# N2_Avionics_board.net
KiCad netlist of a schematic drawn in EasyEDA
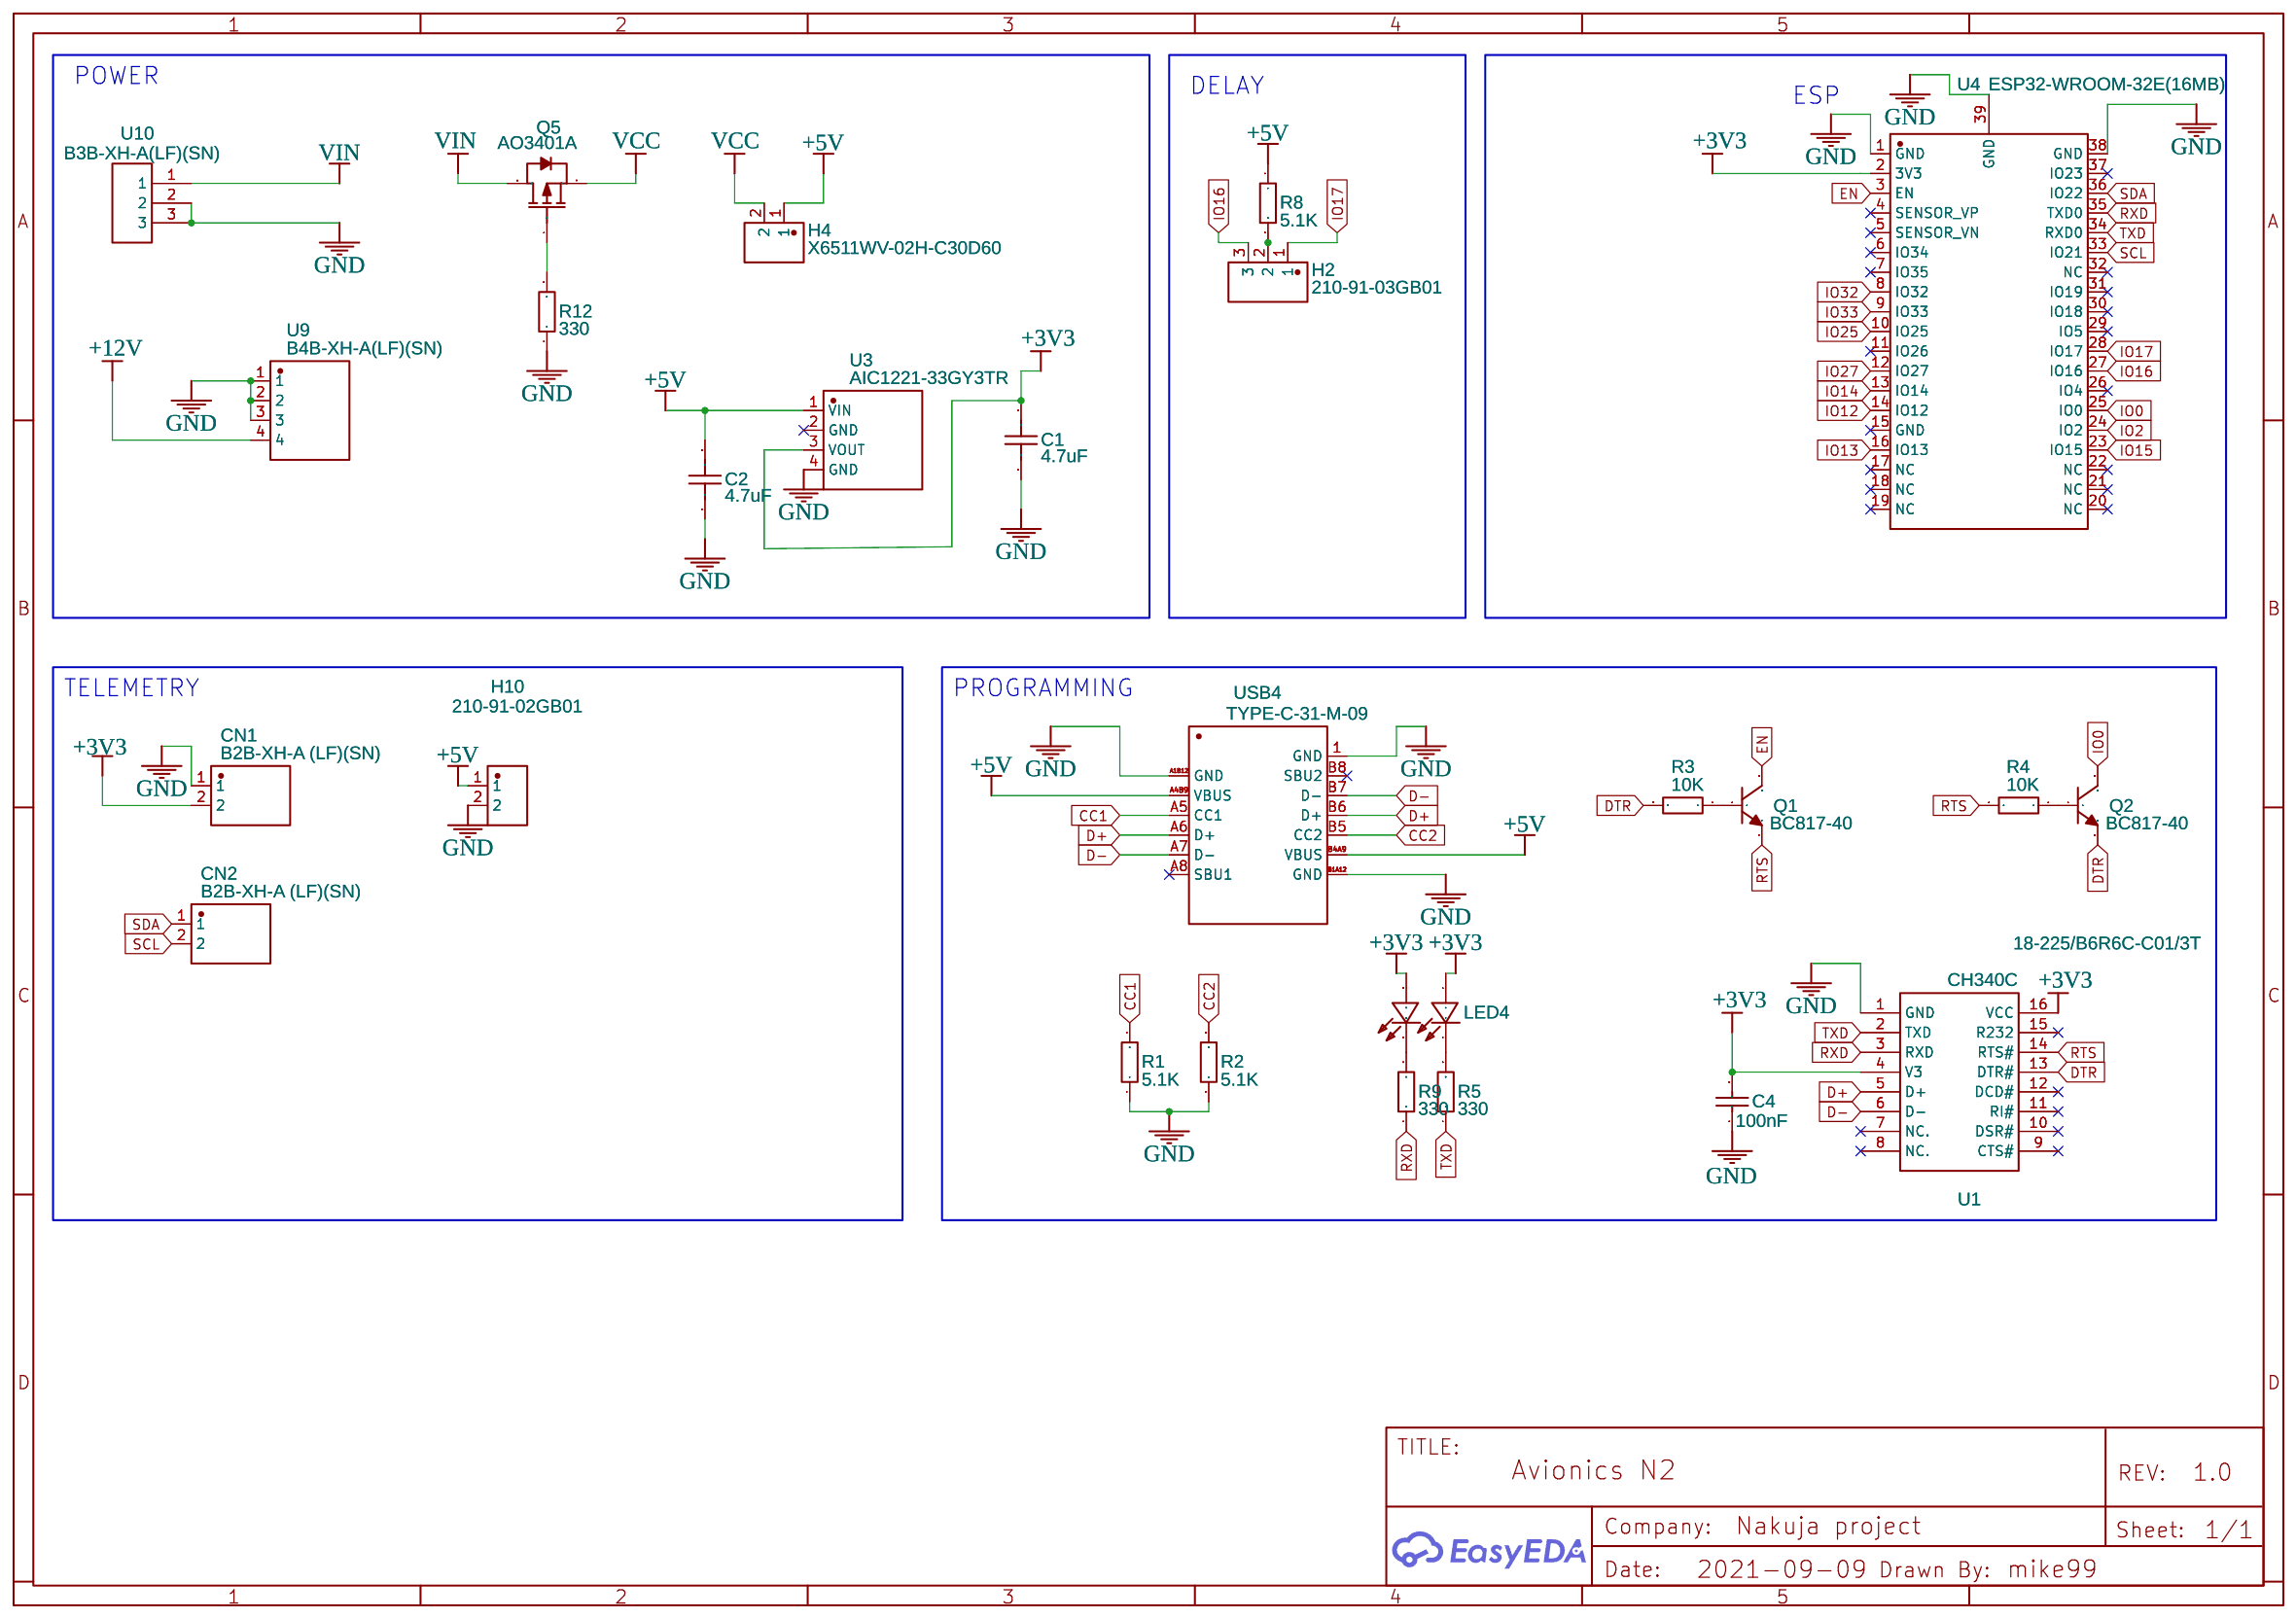
[diagram p0: Sheet_1]
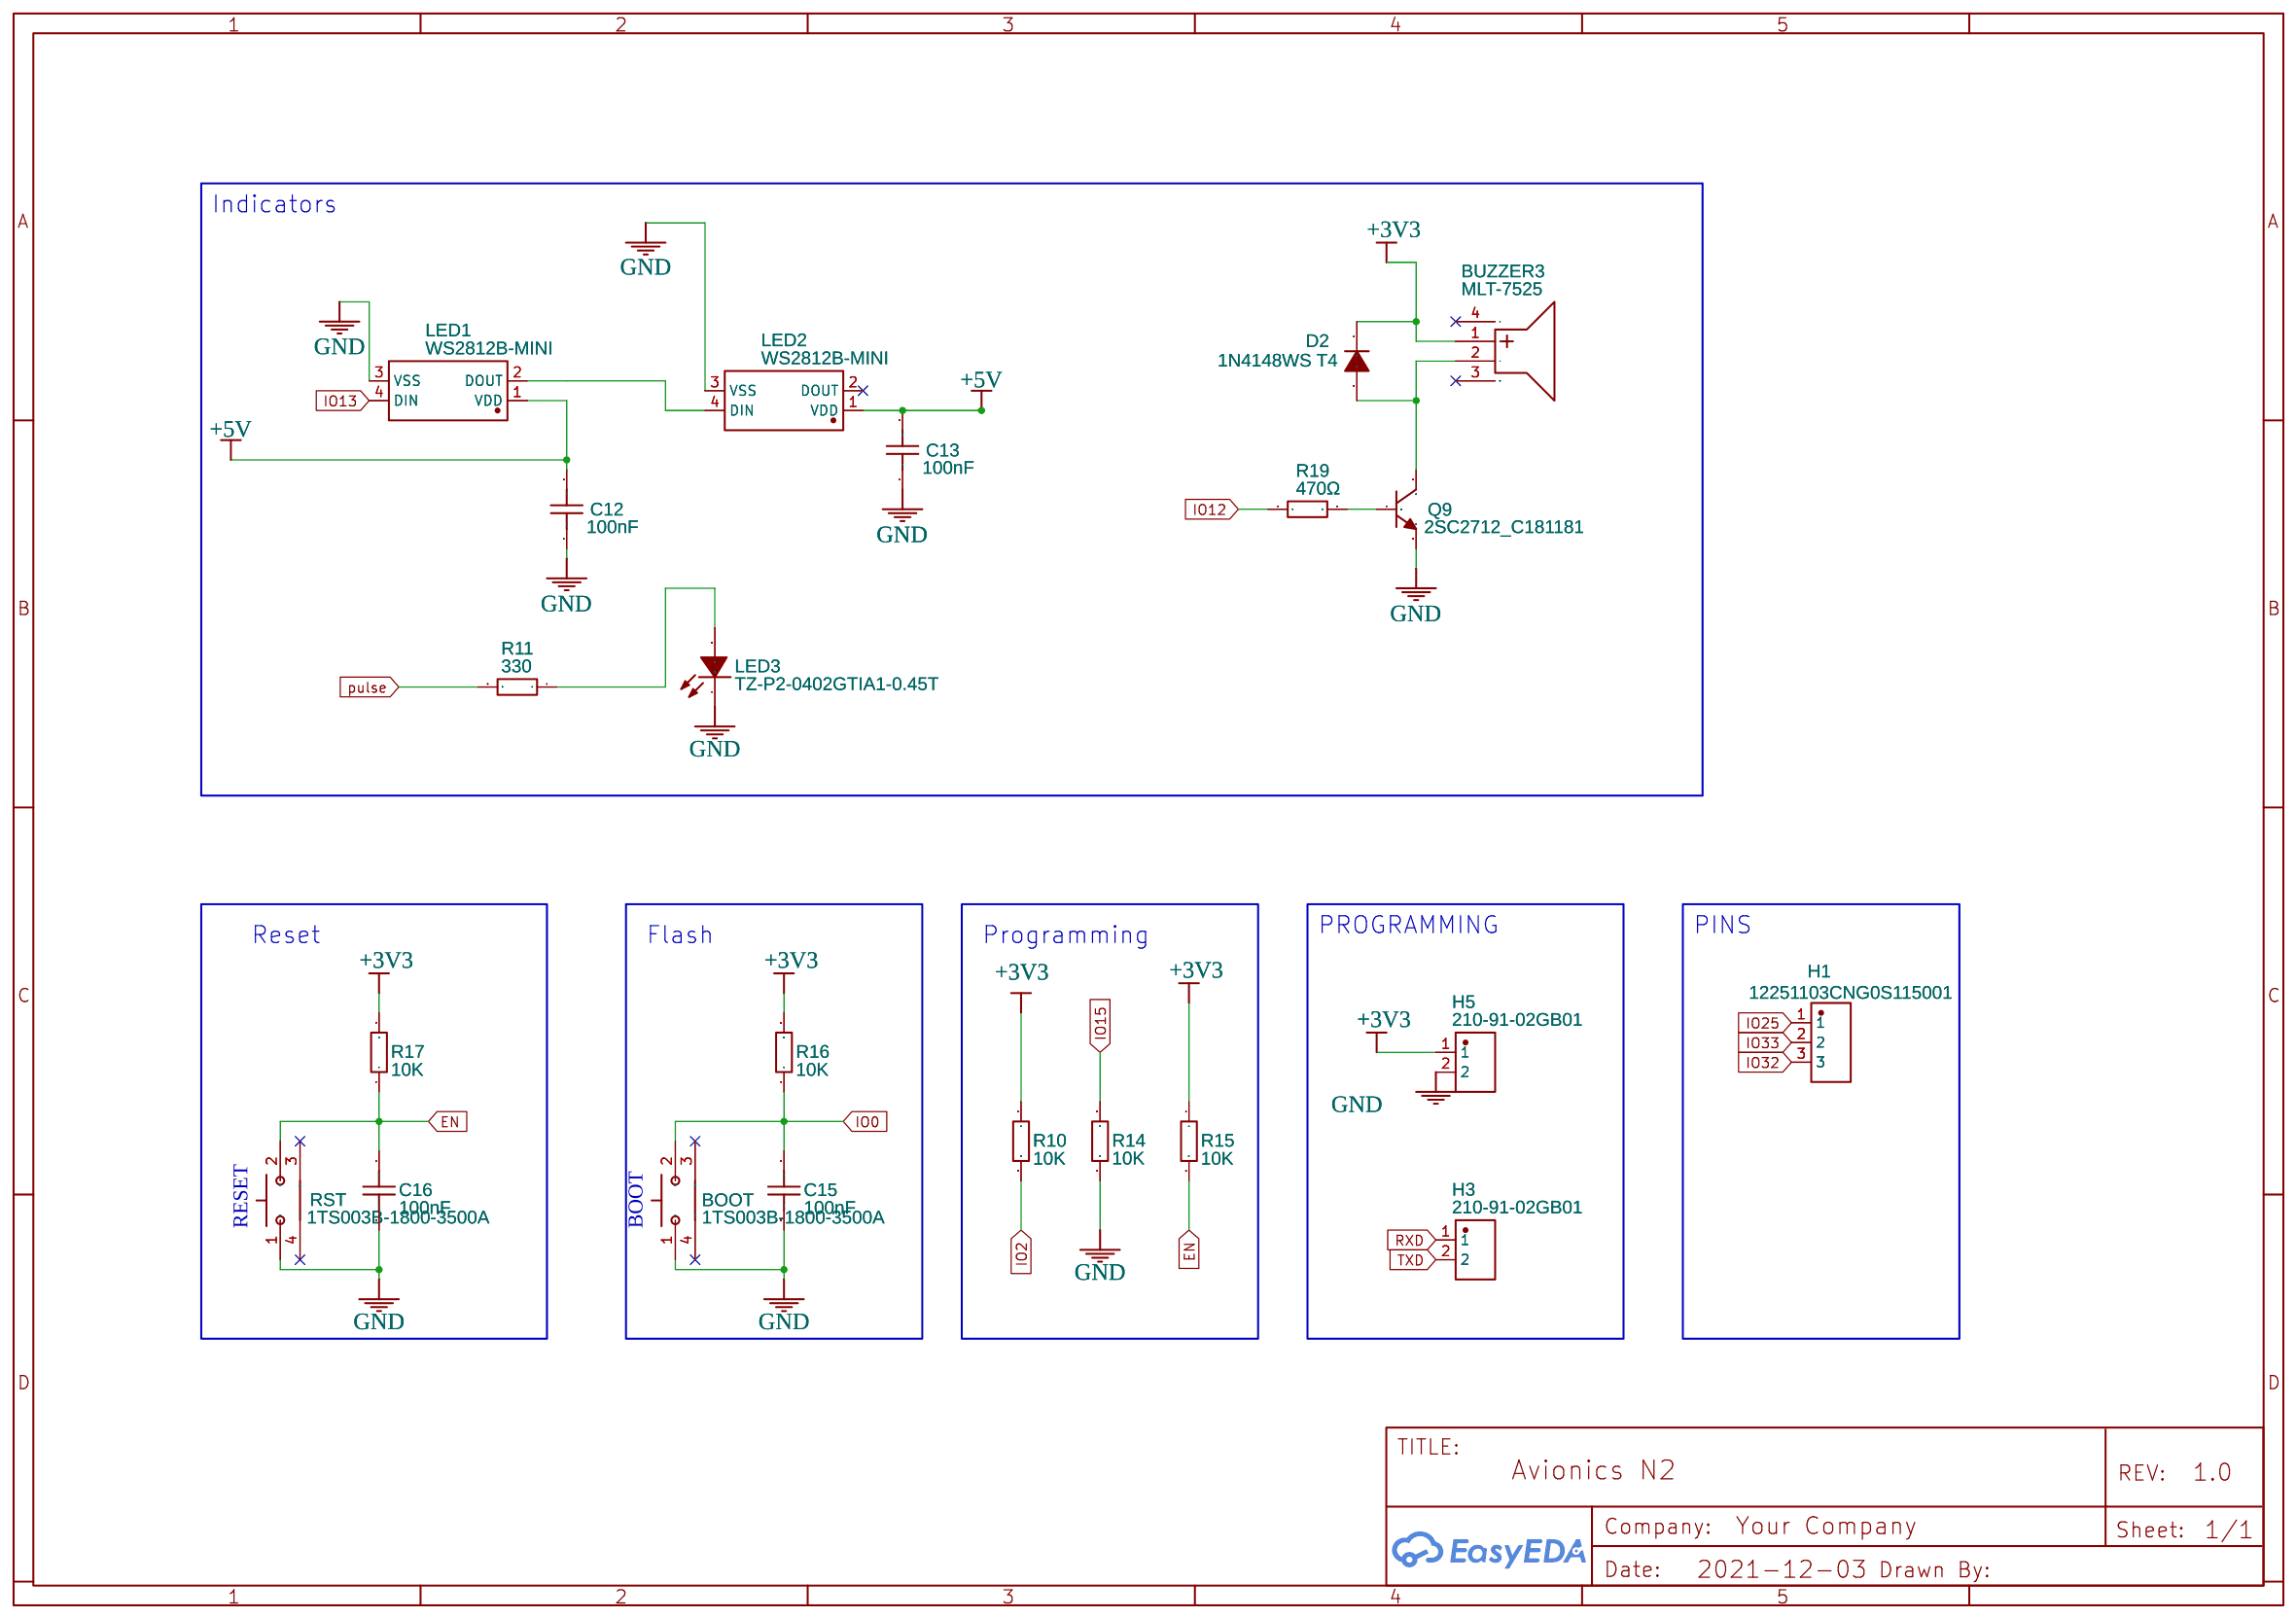
[diagram p1: Sheet_2]
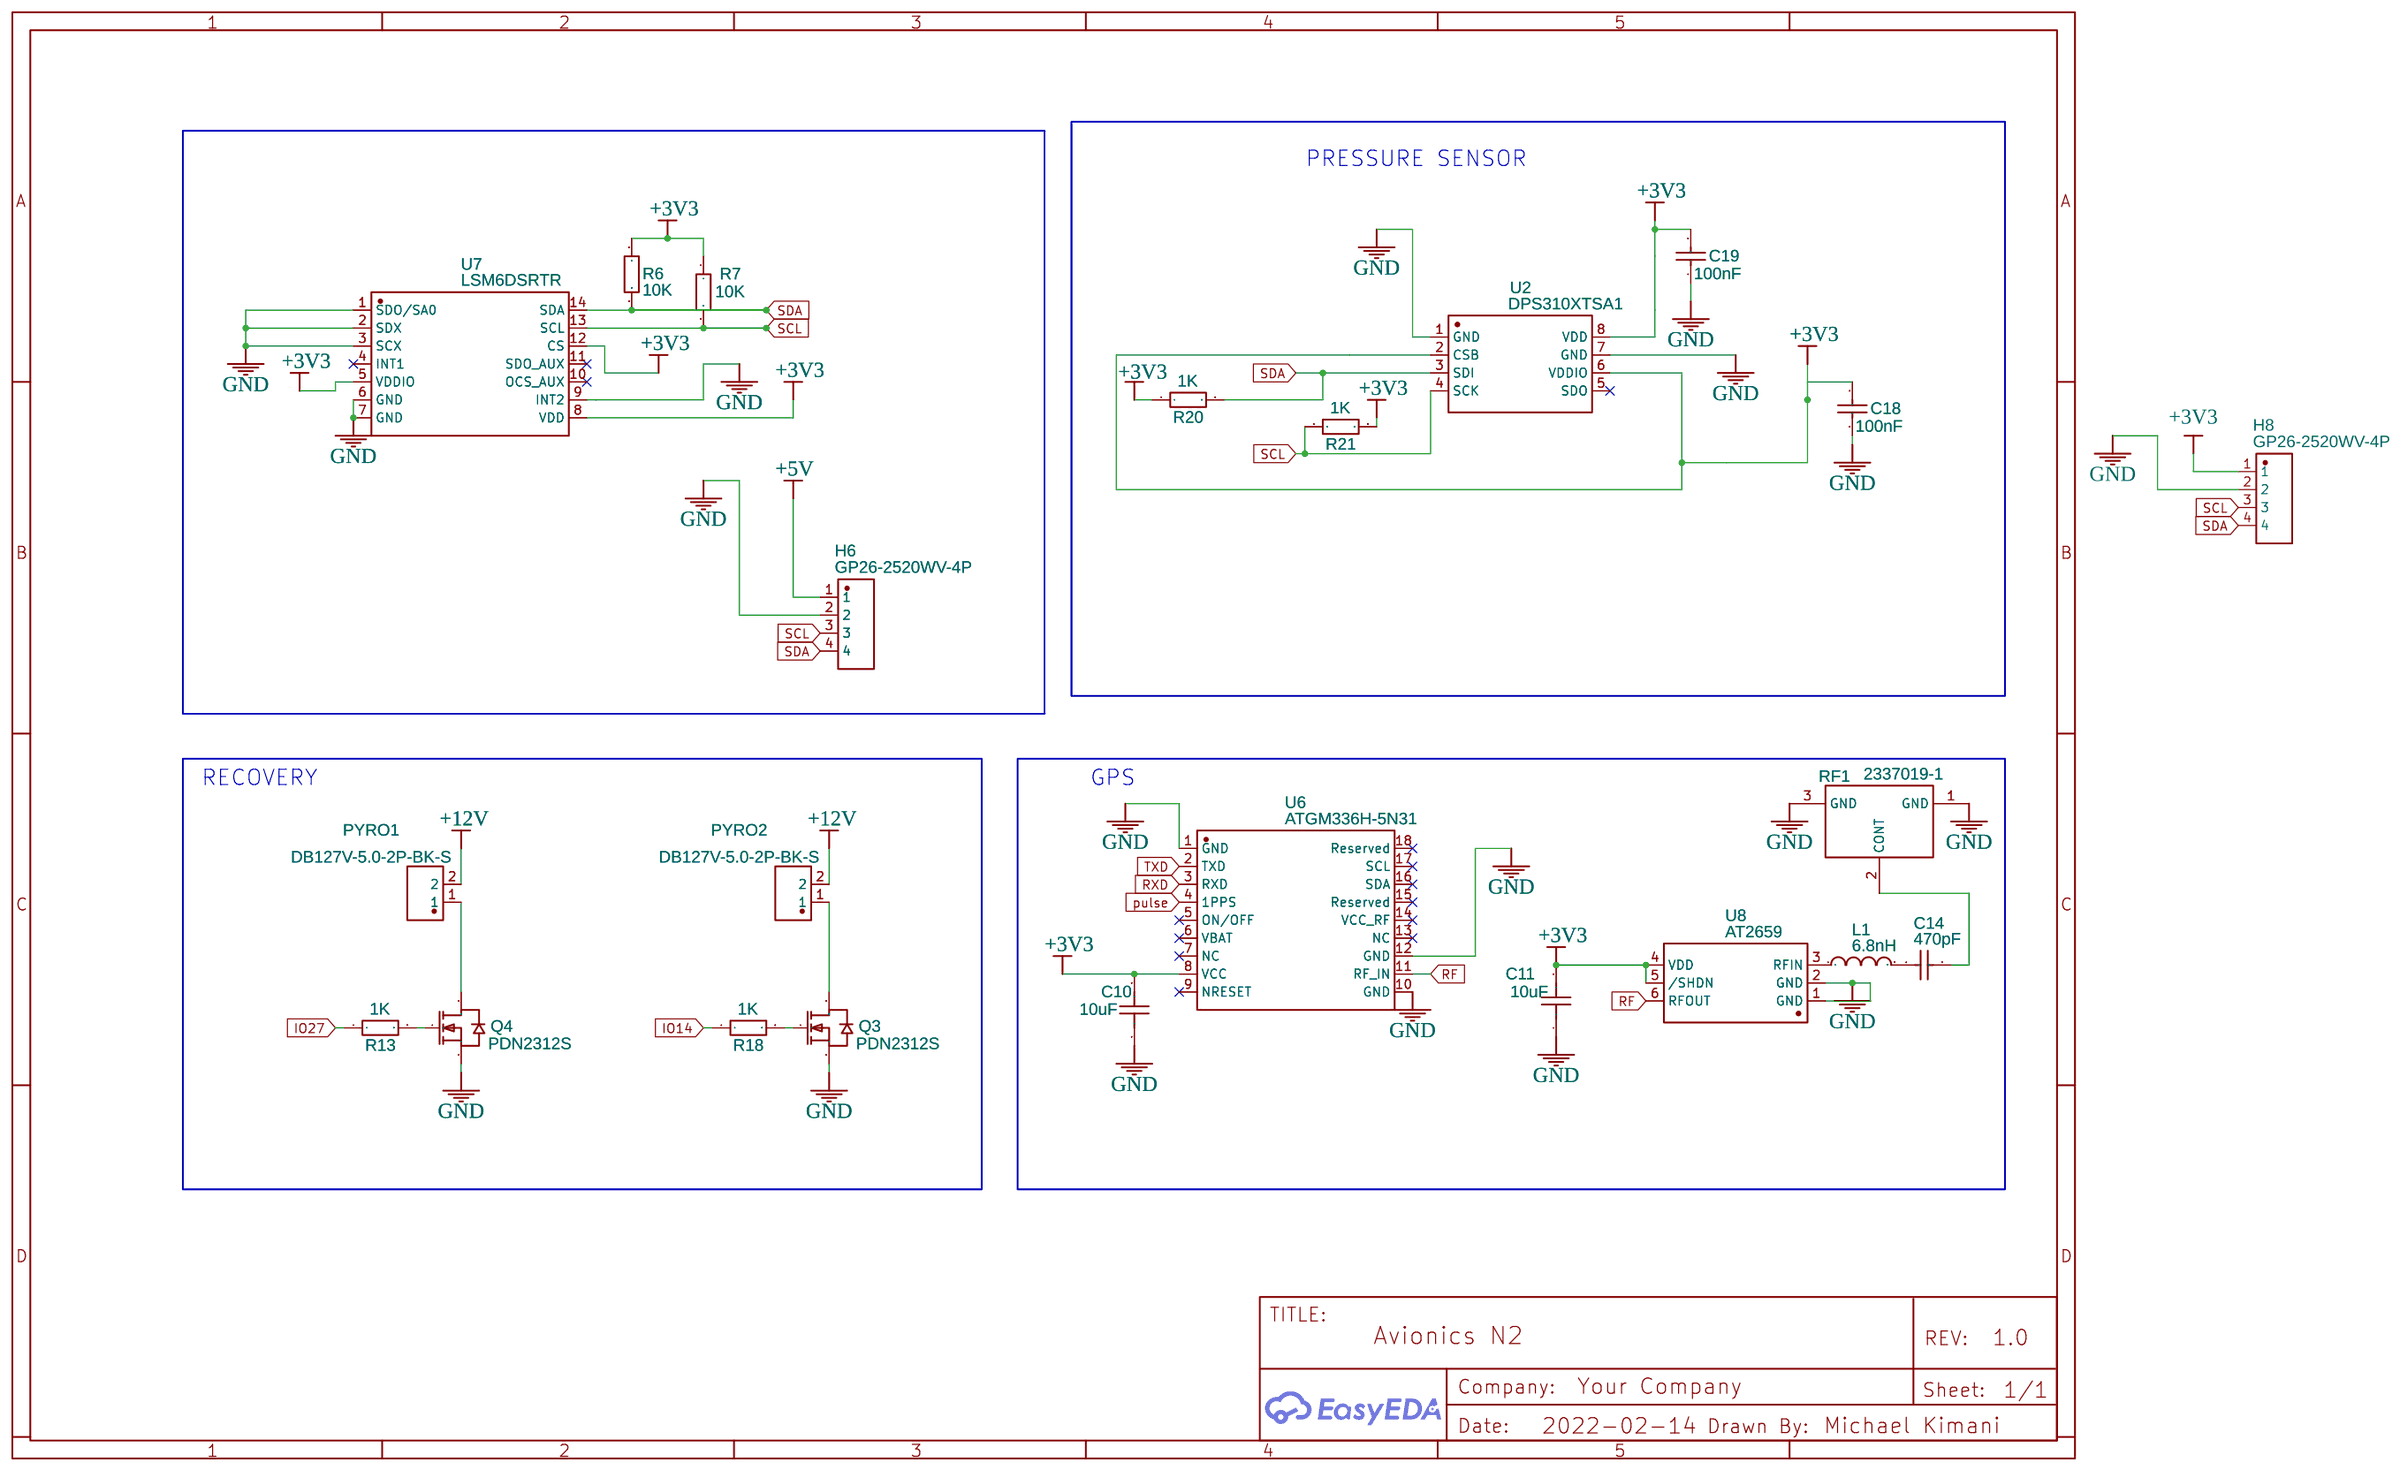
[diagram p2: Sheet_3]

(export (version "E")
  (design (tool "Eeschema 10.0.6"))
  (components
    (comp (ref "C1")
      (value "4.7uF")
      (fields
        (field (name "BOM_Manufacturer Part") "CL05A475MO5NUNC")
        (field (name "BOM_Supplier Part") "C318563")
      )
      (libsource (lib "") (part "CL05A475MO5NUNC"))
    )
    (comp (ref "C2")
      (value "4.7uF")
      (fields
        (field (name "BOM_Manufacturer Part") "CL05A475MO5NUNC")
        (field (name "BOM_Supplier Part") "C318563")
      )
      (libsource (lib "") (part "CL05A475MO5NUNC"))
    )
    (comp (ref "C4")
      (value "100nF")
      (fields
        (field (name "BOM_Manufacturer Part") "0603B104K250")
        (field (name "BOM_Supplier Part") "C83054")
      )
      (libsource (lib "") (part "0603B104K250"))
    )
    (comp (ref "CN1")
      (value "B2B-XH-A (LF)(SN)")
      (fields (field (name "BOM_Supplier Part") "C158012"))
      (libsource (lib "") (part "B2B-XH-A (LF)(SN)"))
    )
    (comp (ref "CN2")
      (value "B2B-XH-A (LF)(SN)")
      (fields (field (name "BOM_Supplier Part") "C158012"))
      (libsource (lib "") (part "B2B-XH-A (LF)(SN)"))
    )
    (comp (ref "H2")
      (value "210-91-03GB01")
      (fields (field (name "BOM_Supplier Part") "C390679"))
      (libsource (lib "") (part "210-91-03GB01"))
    )
    (comp (ref "H4")
      (value "X6511WV-02H-C30D60")
      (fields (field (name "BOM_Supplier Part") "C706874"))
      (libsource (lib "") (part "X6511WV-02H-C30D60"))
    )
    (comp (ref "H10")
      (value "210-91-02GB01")
      (fields (field (name "BOM_Supplier Part") "C390678"))
      (libsource (lib "") (part "210-91-02GB01"))
    )
    (comp (ref "LED4")
      (value "18-225/B6R6C-C01/3T")
      (fields (field (name "BOM_Supplier Part") "C282127"))
      (libsource (lib "") (part "18-225/B6R6C-C01/3T"))
    )
    (comp (ref "Q1")
      (value "BC817-40")
      (fields (field (name "BOM_Supplier Part") "C181151"))
      (libsource (lib "") (part "BC817-40"))
    )
    (comp (ref "Q2")
      (value "BC817-40")
      (fields (field (name "BOM_Supplier Part") "C181151"))
      (libsource (lib "") (part "BC817-40"))
    )
    (comp (ref "Q5")
      (value "AO3401A")
      (fields (field (name "BOM_Supplier Part") "C15127"))
      (libsource (lib "") (part "AO3401A"))
    )
    (comp (ref "R1")
      (value "5.1K")
      (fields
        (field (name "BOM_Manufacturer Part") "0402WGF5101TCE")
        (field (name "BOM_Supplier Part") "C25905")
      )
      (libsource (lib "") (part "0402WGF5101TCE"))
    )
    (comp (ref "R2")
      (value "5.1K")
      (fields
        (field (name "BOM_Manufacturer Part") "0402WGF5101TCE")
        (field (name "BOM_Supplier Part") "C25905")
      )
      (libsource (lib "") (part "0402WGF5101TCE"))
    )
    (comp (ref "R3")
      (value "10K")
      (fields
        (field (name "BOM_Manufacturer Part") "RTT02103JTH")
        (field (name "BOM_Supplier Part") "C102759")
      )
      (libsource (lib "") (part "RTT02103JTH"))
    )
    (comp (ref "R4")
      (value "10K")
      (fields
        (field (name "BOM_Manufacturer Part") "RTT02103JTH")
        (field (name "BOM_Supplier Part") "C102759")
      )
      (libsource (lib "") (part "RTT02103JTH"))
    )
    (comp (ref "R5")
      (value "330")
      (fields
        (field (name "BOM_Manufacturer Part") "0402WGJ0331TCE")
        (field (name "BOM_Supplier Part") "C12246")
      )
      (libsource (lib "") (part "0402WGJ0331TCE"))
    )
    (comp (ref "R8")
      (value "5.1K")
      (fields
        (field (name "BOM_Manufacturer Part") "0402WGF5101TCE")
        (field (name "BOM_Supplier Part") "C25905")
      )
      (libsource (lib "") (part "0402WGF5101TCE_1"))
    )
    (comp (ref "R9")
      (value "330")
      (fields
        (field (name "BOM_Manufacturer Part") "0402WGJ0331TCE")
        (field (name "BOM_Supplier Part") "C12246")
      )
      (libsource (lib "") (part "0402WGJ0331TCE"))
    )
    (comp (ref "R12")
      (value "330")
      (fields
        (field (name "BOM_Manufacturer Part") "0402WGJ0331TCE")
        (field (name "BOM_Supplier Part") "C12246")
      )
      (libsource (lib "") (part "0402WGJ0331TCE"))
    )
    (comp (ref "U1")
      (value "CH340C")
      (fields (field (name "BOM_Supplier Part") "C84681"))
      (libsource (lib "") (part "CH340C"))
    )
    (comp (ref "U3")
      (value "AIC1221-33GY3TR")
      (fields (field (name "BOM_Supplier Part") "C211622"))
      (libsource (lib "") (part "AIC1221-33GY3TR"))
    )
    (comp (ref "U4")
      (value "ESP32-WROOM-32E(16MB)")
      (fields (field (name "BOM_Supplier Part") "C701343"))
      (libsource (lib "") (part "ESP32-WROOM-32E(16MB)"))
    )
    (comp (ref "U9")
      (value "B4B-XH-A(LF)(SN)")
      (fields (field (name "BOM_Supplier Part") "C144395"))
      (libsource (lib "") (part "B4B-XH-A(LF)(SN)"))
    )
    (comp (ref "U10")
      (value "B3B-XH-A(LF)(SN)")
      (fields (field (name "BOM_Supplier Part") "C144394"))
      (libsource (lib "") (part "B3B-XH-A(LF)(SN)"))
    )
    (comp (ref "USB4")
      (value "TYPE-C-31-M-09")
      (fields (field (name "BOM_Supplier Part") "C2689967"))
      (libsource (lib "") (part "TYPE-C-31-M-09"))
    )
    (comp (ref "BOOT")
      (value "1TS003B-1800-3500A")
      (fields (field (name "BOM_Supplier Part") "C255809"))
      (libsource (lib "") (part "1TS003B-1800-3500A_1"))
    )
    (comp (ref "BUZZER3")
      (value "MLT-7525")
      (fields (field (name "BOM_Supplier Part") "C95299"))
      (libsource (lib "") (part "MLT-7525"))
    )
    (comp (ref "C12")
      (value "100nF")
      (fields
        (field (name "BOM_Manufacturer Part") "CL05B104KB54PNC")
        (field (name "BOM_Supplier Part") "C307331")
      )
      (libsource (lib "") (part "CL05B104KB54PNC_1"))
    )
    (comp (ref "C13")
      (value "100nF")
      (fields
        (field (name "BOM_Manufacturer Part") "CL05B104KB54PNC")
        (field (name "BOM_Supplier Part") "C307331")
      )
      (libsource (lib "") (part "CL05B104KB54PNC_1"))
    )
    (comp (ref "C15")
      (value "100nF")
      (fields
        (field (name "BOM_Manufacturer Part") "CL05B104KB54PNC")
        (field (name "BOM_Supplier Part") "C307331")
      )
      (libsource (lib "") (part "CL05B104KB54PNC"))
    )
    (comp (ref "C16")
      (value "100nF")
      (fields
        (field (name "BOM_Manufacturer Part") "CL05B104KB54PNC")
        (field (name "BOM_Supplier Part") "C307331")
      )
      (libsource (lib "") (part "CL05B104KB54PNC"))
    )
    (comp (ref "D2")
      (value "1N4148WS T4")
      (fields (field (name "BOM_Supplier Part") "C2128"))
      (libsource (lib "") (part "1N4148WS T4"))
    )
    (comp (ref "H1")
      (value "12251103CNG0S115001")
      (fields (field (name "BOM_Supplier Part") "C429954"))
      (libsource (lib "") (part "12251103CNG0S115001"))
    )
    (comp (ref "H3")
      (value "210-91-02GB01")
      (fields (field (name "BOM_Supplier Part") "C390678"))
      (libsource (lib "") (part "210-91-02GB01"))
    )
    (comp (ref "H5")
      (value "210-91-02GB01")
      (fields (field (name "BOM_Supplier Part") "C390678"))
      (libsource (lib "") (part "210-91-02GB01"))
    )
    (comp (ref "LED1")
      (value "WS2812B-MINI")
      (fields
        (field (name "BOM_Manufacturer Part") "WS2812B-Mini")
        (field (name "BOM_Supplier Part") "C527089")
      )
      (libsource (lib "") (part "WS2812B-MINI"))
    )
    (comp (ref "LED2")
      (value "WS2812B-MINI")
      (fields
        (field (name "BOM_Manufacturer Part") "WS2812B-Mini")
        (field (name "BOM_Supplier Part") "C527089")
      )
      (libsource (lib "") (part "WS2812B-MINI"))
    )
    (comp (ref "LED3")
      (value "TZ-P2-0402GTIA1-0.45T")
      (fields (field (name "BOM_Supplier Part") "C688877"))
      (libsource (lib "") (part "TZ-P2-0402GTIA1-0.45T"))
    )
    (comp (ref "Q9")
      (value "2SC2712_C181181")
      (fields (field (name "BOM_Manufacturer Part") "2SC2712") (field (name "BOM_Supplier Part") "C181181"))
      (libsource (lib "") (part "2SC2712_C181181"))
    )
    (comp (ref "R10")
      (value "10K")
      (fields
        (field (name "BOM_Manufacturer Part") "RTT02103JTH")
        (field (name "BOM_Supplier Part") "C102759")
      )
      (libsource (lib "") (part "RTT02103JTH_1"))
    )
    (comp (ref "R11")
      (value "330")
      (fields
        (field (name "BOM_Manufacturer Part") "0402WGJ0331TCE")
        (field (name "BOM_Supplier Part") "C12246")
      )
      (libsource (lib "") (part "0402WGJ0331TCE"))
    )
    (comp (ref "R14")
      (value "10K")
      (fields
        (field (name "BOM_Manufacturer Part") "RTT02103JTH")
        (field (name "BOM_Supplier Part") "C102759")
      )
      (libsource (lib "") (part "RTT02103JTH"))
    )
    (comp (ref "R15")
      (value "10K")
      (fields
        (field (name "BOM_Manufacturer Part") "RTT02103JTH")
        (field (name "BOM_Supplier Part") "C102759")
      )
      (libsource (lib "") (part "RTT02103JTH_1"))
    )
    (comp (ref "R16")
      (value "10K")
      (fields
        (field (name "BOM_Manufacturer Part") "RTT02103JTH")
        (field (name "BOM_Supplier Part") "C102759")
      )
      (libsource (lib "") (part "RTT02103JTH"))
    )
    (comp (ref "R17")
      (value "10K")
      (fields
        (field (name "BOM_Manufacturer Part") "RTT02103JTH")
        (field (name "BOM_Supplier Part") "C102759")
      )
      (libsource (lib "") (part "RTT02103JTH"))
    )
    (comp (ref "R19")
      (value "470Ω")
      (fields
        (field (name "BOM_Manufacturer Part") "0402WGF4700TCE")
        (field (name "BOM_Supplier Part") "C25117")
      )
      (libsource (lib "") (part "0402WGF4700TCE"))
    )
    (comp (ref "RST")
      (value "1TS003B-1800-3500A")
      (fields (field (name "BOM_Supplier Part") "C255809"))
      (libsource (lib "") (part "1TS003B-1800-3500A"))
    )
    (comp (ref "C10")
      (value "10uF")
      (fields
        (field (name "BOM_Manufacturer Part") "CL05A106MQ8NUB8")
        (field (name "BOM_Supplier Part") "C307416")
      )
      (libsource (lib "") (part "CL05A106MQ8NUB8"))
    )
    (comp (ref "C11")
      (value "10uF")
      (fields
        (field (name "BOM_Manufacturer Part") "CL05A106MQ8NUB8")
        (field (name "BOM_Supplier Part") "C307416")
      )
      (libsource (lib "") (part "CL05A106MQ8NUB8"))
    )
    (comp (ref "C14")
      (value "470pF")
      (fields
        (field (name "BOM_Manufacturer Part") "0402B471K500NT")
        (field (name "BOM_Supplier Part") "C1537")
      )
      (libsource (lib "") (part "0402B471K500NT"))
    )
    (comp (ref "C18")
      (value "100nF")
      (fields
        (field (name "BOM_Manufacturer Part") "0603B104K250")
        (field (name "BOM_Supplier Part") "C83054")
      )
      (libsource (lib "") (part "0603B104K250"))
    )
    (comp (ref "C19")
      (value "100nF")
      (fields
        (field (name "BOM_Manufacturer Part") "0603B104K250")
        (field (name "BOM_Supplier Part") "C83054")
      )
      (libsource (lib "") (part "0603B104K250"))
    )
    (comp (ref "H6")
      (value "GP26-2520WV-4P")
      (fields (field (name "BOM_Supplier Part") "C2681739"))
      (libsource (lib "") (part "GP26-2520WV-4P"))
    )
    (comp (ref "H8")
      (value "GP26-2520WV-4P")
      (fields (field (name "BOM_Supplier Part") "C2681739"))
      (libsource (lib "") (part "GP26-2520WV-4P"))
    )
    (comp (ref "L1")
      (value "6.8nH")
      (fields
        (field (name "BOM_Manufacturer Part") "SDCL1005C6N8JTDF")
        (field (name "BOM_Supplier Part") "C32041")
      )
      (libsource (lib "") (part "SDCL1005C6N8JTDF"))
    )
    (comp (ref "PYRO1")
      (value "DB127V-5.0-2P-BK-S")
      (fields (field (name "BOM_Supplier Part") "C430623"))
      (libsource (lib "") (part "DB127V-5.0-2P-BK-S"))
    )
    (comp (ref "PYRO2")
      (value "DB127V-5.0-2P-BK-S")
      (fields (field (name "BOM_Supplier Part") "C430623"))
      (libsource (lib "") (part "DB127V-5.0-2P-BK-S"))
    )
    (comp (ref "Q3")
      (value "PDN2312S")
      (fields (field (name "BOM_Supplier Part") "C441842"))
      (libsource (lib "") (part "PDN2312S"))
    )
    (comp (ref "Q4")
      (value "PDN2312S")
      (fields (field (name "BOM_Supplier Part") "C441842"))
      (libsource (lib "") (part "PDN2312S"))
    )
    (comp (ref "R6")
      (value "10K")
      (fields
        (field (name "BOM_Manufacturer Part") "RTT02103JTH")
        (field (name "BOM_Supplier Part") "C102759")
      )
      (libsource (lib "") (part "RTT02103JTH"))
    )
    (comp (ref "R7")
      (value "10K")
      (fields
        (field (name "BOM_Manufacturer Part") "RTT02103JTH")
        (field (name "BOM_Supplier Part") "C102759")
      )
      (libsource (lib "") (part "RTT02103JTH"))
    )
    (comp (ref "R13")
      (value "1K")
      (fields
        (field (name "BOM_Manufacturer Part") "0402WGF1001TCE")
        (field (name "BOM_Supplier Part") "C11702")
      )
      (libsource (lib "") (part "0402WGF1001TCE"))
    )
    (comp (ref "R18")
      (value "1K")
      (fields
        (field (name "BOM_Manufacturer Part") "0402WGF1001TCE")
        (field (name "BOM_Supplier Part") "C11702")
      )
      (libsource (lib "") (part "0402WGF1001TCE"))
    )
    (comp (ref "R20")
      (value "1K")
      (fields
        (field (name "BOM_Manufacturer Part") "0402WGF1001TCE")
        (field (name "BOM_Supplier Part") "C11702")
      )
      (libsource (lib "") (part "0402WGF1001TCE"))
    )
    (comp (ref "R21")
      (value "1K")
      (fields
        (field (name "BOM_Manufacturer Part") "0402WGF1001TCE")
        (field (name "BOM_Supplier Part") "C11702")
      )
      (libsource (lib "") (part "0402WGF1001TCE"))
    )
    (comp (ref "RF1")
      (value "2337019-1")
      (fields (field (name "BOM_Supplier Part") "C434807"))
      (libsource (lib "") (part "2337019-1"))
    )
    (comp (ref "U2")
      (value "DPS310XTSA1")
      (fields (field (name "BOM_Supplier Part") "C130156"))
      (libsource (lib "") (part "DPS310XTSA1"))
    )
    (comp (ref "U6")
      (value "ATGM336H-5N31")
      (fields (field (name "BOM_Supplier Part") "C90770"))
      (libsource (lib "") (part "ATGM336H-5N31"))
    )
    (comp (ref "U7")
      (value "LSM6DSRTR")
      (fields (field (name "BOM_Supplier Part") "C784817"))
      (libsource (lib "") (part "LSM6DSRTR"))
    )
    (comp (ref "U8")
      (value "AT2659")
      (fields (field (name "BOM_Supplier Part") "C92450"))
      (libsource (lib "") (part "AT2659"))
    )
  )
  (nets
    (net (code "1") (name "+3V3") (class "Default")
      (node (ref "BUZZER3") (pin "1") (pinfunction "+_1") (pintype "unspecified"))
      (node (ref "C1") (pin "2") (pinfunction "2_2") (pintype "unspecified"))
      (node (ref "C10") (pin "2") (pinfunction "2_2") (pintype "unspecified"))
      (node (ref "C11") (pin "2") (pinfunction "2_2") (pintype "unspecified"))
      (node (ref "C18") (pin "2") (pinfunction "2_2") (pintype "input"))
      (node (ref "C19") (pin "2") (pinfunction "2_2") (pintype "input"))
      (node (ref "C4") (pin "2") (pinfunction "2_2") (pintype "input"))
      (node (ref "CN1") (pin "2") (pinfunction "2_2") (pintype "unspecified"))
      (node (ref "D2") (pin "1") (pinfunction "K_1") (pintype "unspecified"))
      (node (ref "H5") (pin "1") (pinfunction "1_1") (pintype "unspecified"))
      (node (ref "H8") (pin "1") (pinfunction "1_1") (pintype "unspecified"))
      (node (ref "LED4") (pin "1") (pinfunction "1_1") (pintype "unspecified"))
      (node (ref "LED4") (pin "2") (pinfunction "2_2") (pintype "unspecified"))
      (node (ref "R10") (pin "1") (pinfunction "1_1") (pintype "input"))
      (node (ref "R15") (pin "1") (pinfunction "1_1") (pintype "input"))
      (node (ref "R16") (pin "2") (pinfunction "2_2") (pintype "input"))
      (node (ref "R17") (pin "2") (pinfunction "2_2") (pintype "input"))
      (node (ref "R20") (pin "1") (pinfunction "1_1") (pintype "input"))
      (node (ref "R21") (pin "2") (pinfunction "2_2") (pintype "input"))
      (node (ref "R6") (pin "1") (pinfunction "1_1") (pintype "input"))
      (node (ref "R7") (pin "1") (pinfunction "1_1") (pintype "input"))
      (node (ref "U1") (pin "16") (pinfunction "VCC_16") (pintype "unspecified"))
      (node (ref "U1") (pin "4") (pinfunction "V3_4") (pintype "unspecified"))
      (node (ref "U2") (pin "2") (pinfunction "CSB_2") (pintype "unspecified"))
      (node (ref "U2") (pin "6") (pinfunction "VDDIO_6") (pintype "unspecified"))
      (node (ref "U2") (pin "8") (pinfunction "VDD_8") (pintype "unspecified"))
      (node (ref "U3") (pin "3") (pinfunction "VOUT_3") (pintype "unspecified"))
      (node (ref "U4") (pin "2") (pinfunction "3V3_2") (pintype "unspecified"))
      (node (ref "U6") (pin "8") (pinfunction "VCC_8") (pintype "unspecified"))
      (node (ref "U7") (pin "12") (pinfunction "CS_12") (pintype "unspecified"))
      (node (ref "U7") (pin "5") (pinfunction "VDDIO_5") (pintype "unspecified"))
      (node (ref "U7") (pin "8") (pinfunction "VDD_8") (pintype "unspecified"))
      (node (ref "U8") (pin "4") (pinfunction "VDD_4") (pintype "unspecified"))
      (node (ref "U8") (pin "5") (pinfunction "/SHDN_5") (pintype "unspecified"))
    )
    (net (code "2") (name "+5V") (class "Default")
      (node (ref "C12") (pin "2") (pinfunction "2_2") (pintype "unspecified"))
      (node (ref "C13") (pin "2") (pinfunction "2_2") (pintype "unspecified"))
      (node (ref "C2") (pin "2") (pinfunction "2_2") (pintype "unspecified"))
      (node (ref "H10") (pin "1") (pinfunction "1_1") (pintype "unspecified"))
      (node (ref "H4") (pin "1") (pinfunction "1_1") (pintype "unspecified"))
      (node (ref "H6") (pin "1") (pinfunction "1_1") (pintype "unspecified"))
      (node (ref "LED1") (pin "1") (pinfunction "VDD_1") (pintype "unspecified"))
      (node (ref "LED2") (pin "1") (pinfunction "VDD_1") (pintype "unspecified"))
      (node (ref "R8") (pin "1") (pinfunction "1_1") (pintype "input"))
      (node (ref "U3") (pin "1") (pinfunction "VIN_1") (pintype "unspecified"))
      (node (ref "USB4") (pin "A4B9") (pinfunction "VBUS_A4B9") (pintype "unspecified"))
      (node (ref "USB4") (pin "B4A9") (pinfunction "VBUS_B4A9") (pintype "unspecified"))
    )
    (net (code "3") (name "+12V") (class "Default")
      (node (ref "PYRO1") (pin "2") (pinfunction "2_2") (pintype "unspecified"))
      (node (ref "PYRO2") (pin "2") (pinfunction "2_2") (pintype "unspecified"))
      (node (ref "U9") (pin "4") (pinfunction "4_4") (pintype "unspecified"))
    )
    (net (code "4") (name "CC1") (class "Default")
      (node (ref "R1") (pin "2") (pinfunction "2_2") (pintype "input"))
      (node (ref "USB4") (pin "A5") (pinfunction "CC1_A5") (pintype "unspecified"))
    )
    (net (code "5") (name "CC2") (class "Default")
      (node (ref "R2") (pin "2") (pinfunction "2_2") (pintype "input"))
      (node (ref "USB4") (pin "B5") (pinfunction "CC2_B5") (pintype "unspecified"))
    )
    (net (code "6") (name "D+") (class "Default")
      (node (ref "U1") (pin "5") (pinfunction "D+_5") (pintype "unspecified"))
      (node (ref "USB4") (pin "A6") (pinfunction "D+_A6") (pintype "unspecified"))
      (node (ref "USB4") (pin "B6") (pinfunction "D+_B6") (pintype "unspecified"))
    )
    (net (code "7") (name "D-") (class "Default")
      (node (ref "U1") (pin "6") (pinfunction "D-_6") (pintype "unspecified"))
      (node (ref "USB4") (pin "A7") (pinfunction "D-_A7") (pintype "unspecified"))
      (node (ref "USB4") (pin "B7") (pinfunction "D-_B7") (pintype "unspecified"))
    )
    (net (code "8") (name "DTR") (class "Default")
      (node (ref "Q2") (pin "2") (pinfunction "2_2") (pintype "input"))
      (node (ref "R3") (pin "2") (pinfunction "2_2") (pintype "input"))
      (node (ref "U1") (pin "13") (pinfunction "DTR#_13") (pintype "unspecified"))
    )
    (net (code "9") (name "EN") (class "Default")
      (node (ref "C16") (pin "1") (pinfunction "1_1") (pintype "unspecified"))
      (node (ref "Q1") (pin "3") (pinfunction "3_3") (pintype "input"))
      (node (ref "R15") (pin "2") (pinfunction "2_2") (pintype "input"))
      (node (ref "R17") (pin "1") (pinfunction "1_1") (pintype "input"))
      (node (ref "RST") (pin "2") (pinfunction "2_2") (pintype "unspecified"))
      (node (ref "U4") (pin "3") (pinfunction "EN_3") (pintype "unspecified"))
    )
    (net (code "10") (name "GND") (class "Default")
      (node (ref "BOOT") (pin "1") (pinfunction "1_1") (pintype "unspecified"))
      (node (ref "C1") (pin "1") (pinfunction "1_1") (pintype "unspecified"))
      (node (ref "C10") (pin "1") (pinfunction "1_1") (pintype "unspecified"))
      (node (ref "C11") (pin "1") (pinfunction "1_1") (pintype "unspecified"))
      (node (ref "C12") (pin "1") (pinfunction "1_1") (pintype "unspecified"))
      (node (ref "C13") (pin "1") (pinfunction "1_1") (pintype "unspecified"))
      (node (ref "C15") (pin "2") (pinfunction "2_2") (pintype "unspecified"))
      (node (ref "C16") (pin "2") (pinfunction "2_2") (pintype "unspecified"))
      (node (ref "C18") (pin "1") (pinfunction "1_1") (pintype "input"))
      (node (ref "C19") (pin "1") (pinfunction "1_1") (pintype "input"))
      (node (ref "C2") (pin "1") (pinfunction "1_1") (pintype "unspecified"))
      (node (ref "C4") (pin "1") (pinfunction "1_1") (pintype "input"))
      (node (ref "CN1") (pin "1") (pinfunction "1_1") (pintype "unspecified"))
      (node (ref "H10") (pin "2") (pinfunction "2_2") (pintype "unspecified"))
      (node (ref "H5") (pin "2") (pinfunction "2_2") (pintype "unspecified"))
      (node (ref "H6") (pin "2") (pinfunction "2_2") (pintype "unspecified"))
      (node (ref "H8") (pin "2") (pinfunction "2_2") (pintype "unspecified"))
      (node (ref "LED1") (pin "3") (pinfunction "VSS_3") (pintype "unspecified"))
      (node (ref "LED2") (pin "3") (pinfunction "VSS_3") (pintype "unspecified"))
      (node (ref "LED3") (pin "1") (pinfunction "C_1") (pintype "unspecified"))
      (node (ref "Q3") (pin "2") (pinfunction "S_2") (pintype "unspecified"))
      (node (ref "Q4") (pin "2") (pinfunction "S_2") (pintype "unspecified"))
      (node (ref "Q9") (pin "2") (pinfunction "E_2") (pintype "input"))
      (node (ref "R1") (pin "1") (pinfunction "1_1") (pintype "input"))
      (node (ref "R12") (pin "1") (pinfunction "1_1") (pintype "input"))
      (node (ref "R14") (pin "1") (pinfunction "1_1") (pintype "input"))
      (node (ref "R2") (pin "1") (pinfunction "1_1") (pintype "input"))
      (node (ref "RF1") (pin "1") (pinfunction "GND_1") (pintype "unspecified"))
      (node (ref "RF1") (pin "3") (pinfunction "GND_3") (pintype "unspecified"))
      (node (ref "RST") (pin "1") (pinfunction "1_1") (pintype "unspecified"))
      (node (ref "U1") (pin "1") (pinfunction "GND_1") (pintype "unspecified"))
      (node (ref "U10") (pin "2") (pinfunction "2_2") (pintype "unspecified"))
      (node (ref "U10") (pin "3") (pinfunction "3_3") (pintype "unspecified"))
      (node (ref "U2") (pin "1") (pinfunction "GND_1") (pintype "unspecified"))
      (node (ref "U2") (pin "7") (pinfunction "GND_7") (pintype "unspecified"))
      (node (ref "U3") (pin "4") (pinfunction "GND_4") (pintype "unspecified"))
      (node (ref "U4") (pin "1") (pinfunction "GND_1") (pintype "unspecified"))
      (node (ref "U4") (pin "38") (pinfunction "GND_38") (pintype "unspecified"))
      (node (ref "U4") (pin "39") (pinfunction "GND_39") (pintype "unspecified"))
      (node (ref "U6") (pin "1") (pinfunction "GND_1") (pintype "unspecified"))
      (node (ref "U6") (pin "10") (pinfunction "GND_10") (pintype "unspecified"))
      (node (ref "U6") (pin "12") (pinfunction "GND_12") (pintype "unspecified"))
      (node (ref "U7") (pin "1") (pinfunction "SDO/SA0_1") (pintype "unspecified"))
      (node (ref "U7") (pin "2") (pinfunction "SDX_2") (pintype "unspecified"))
      (node (ref "U7") (pin "3") (pinfunction "SCX_3") (pintype "unspecified"))
      (node (ref "U7") (pin "6") (pinfunction "GND_6") (pintype "unspecified"))
      (node (ref "U7") (pin "7") (pinfunction "GND_7") (pintype "unspecified"))
      (node (ref "U7") (pin "9") (pinfunction "INT2_9") (pintype "unspecified"))
      (node (ref "U8") (pin "1") (pinfunction "GND_1") (pintype "unspecified"))
      (node (ref "U8") (pin "2") (pinfunction "GND_2") (pintype "unspecified"))
      (node (ref "U9") (pin "1") (pinfunction "1_1") (pintype "unspecified"))
      (node (ref "U9") (pin "2") (pinfunction "2_2") (pintype "unspecified"))
      (node (ref "U9") (pin "3") (pinfunction "3_3") (pintype "unspecified"))
      (node (ref "USB4") (pin "1") (pinfunction "GND_1") (pintype "unspecified"))
      (node (ref "USB4") (pin "A1B12") (pinfunction "GND_A1B12") (pintype "unspecified"))
      (node (ref "USB4") (pin "B1A12") (pinfunction "GND_B1A12") (pintype "unspecified"))
    )
    (net (code "11") (name "IO0") (class "Default")
      (node (ref "BOOT") (pin "2") (pinfunction "2_2") (pintype "unspecified"))
      (node (ref "C15") (pin "1") (pinfunction "1_1") (pintype "unspecified"))
      (node (ref "Q2") (pin "3") (pinfunction "3_3") (pintype "input"))
      (node (ref "R16") (pin "1") (pinfunction "1_1") (pintype "input"))
      (node (ref "U4") (pin "25") (pinfunction "IO0_25") (pintype "unspecified"))
    )
    (net (code "12") (name "IO2") (class "Default")
      (node (ref "R10") (pin "2") (pinfunction "2_2") (pintype "input"))
      (node (ref "U4") (pin "24") (pinfunction "IO2_24") (pintype "unspecified"))
    )
    (net (code "13") (name "IO12") (class "Default")
      (node (ref "R19") (pin "1") (pinfunction "1_1") (pintype "input"))
      (node (ref "U4") (pin "14") (pinfunction "IO12_14") (pintype "unspecified"))
    )
    (net (code "14") (name "IO13") (class "Default")
      (node (ref "LED1") (pin "4") (pinfunction "DIN_4") (pintype "unspecified"))
      (node (ref "U4") (pin "16") (pinfunction "IO13_16") (pintype "unspecified"))
    )
    (net (code "15") (name "IO14") (class "Default")
      (node (ref "R18") (pin "1") (pinfunction "1_1") (pintype "input"))
      (node (ref "U4") (pin "13") (pinfunction "IO14_13") (pintype "unspecified"))
    )
    (net (code "16") (name "IO15") (class "Default")
      (node (ref "R14") (pin "2") (pinfunction "2_2") (pintype "input"))
      (node (ref "U4") (pin "23") (pinfunction "IO15_23") (pintype "unspecified"))
    )
    (net (code "17") (name "IO16") (class "Default")
      (node (ref "H2") (pin "3") (pinfunction "3_3") (pintype "unspecified"))
      (node (ref "U4") (pin "27") (pinfunction "IO16_27") (pintype "unspecified"))
    )
    (net (code "18") (name "IO17") (class "Default")
      (node (ref "H2") (pin "1") (pinfunction "1_1") (pintype "unspecified"))
      (node (ref "U4") (pin "28") (pinfunction "IO17_28") (pintype "unspecified"))
    )
    (net (code "19") (name "IO25") (class "Default")
      (node (ref "H1") (pin "1") (pinfunction "1_1") (pintype "unspecified"))
      (node (ref "U4") (pin "10") (pinfunction "IO25_10") (pintype "unspecified"))
    )
    (net (code "20") (name "IO27") (class "Default")
      (node (ref "R13") (pin "1") (pinfunction "1_1") (pintype "input"))
      (node (ref "U4") (pin "12") (pinfunction "IO27_12") (pintype "unspecified"))
    )
    (net (code "21") (name "IO32") (class "Default")
      (node (ref "H1") (pin "3") (pinfunction "3_3") (pintype "unspecified"))
      (node (ref "U4") (pin "8") (pinfunction "IO32_8") (pintype "unspecified"))
    )
    (net (code "22") (name "IO33") (class "Default")
      (node (ref "H1") (pin "2") (pinfunction "2_2") (pintype "unspecified"))
      (node (ref "U4") (pin "9") (pinfunction "IO33_9") (pintype "unspecified"))
    )
    (net (code "23") (name "Net-(BUZZER3--)") (class "Default")
      (node (ref "BUZZER3") (pin "2") (pinfunction "-_2") (pintype "unspecified"))
      (node (ref "D2") (pin "2") (pinfunction "A_2") (pintype "unspecified"))
      (node (ref "Q9") (pin "3") (pinfunction "C_3") (pintype "input"))
    )
    (net (code "24") (name "Net-(C14-Pad1)") (class "Default")
      (node (ref "C14") (pin "1") (pinfunction "1_1") (pintype "input"))
      (node (ref "L1") (pin "2") (pinfunction "2_2") (pintype "unspecified"))
    )
    (net (code "25") (name "Net-(H2-Pad2)") (class "Default")
      (node (ref "H2") (pin "2") (pinfunction "2_2") (pintype "unspecified"))
      (node (ref "R8") (pin "2") (pinfunction "2_2") (pintype "input"))
    )
    (net (code "26") (name "Net-(LED1-DOUT)") (class "Default")
      (node (ref "LED1") (pin "2") (pinfunction "DOUT_2") (pintype "unspecified"))
      (node (ref "LED2") (pin "4") (pinfunction "DIN_4") (pintype "unspecified"))
    )
    (net (code "27") (name "Net-(LED3-A)") (class "Default")
      (node (ref "LED3") (pin "2") (pinfunction "A_2") (pintype "unspecified"))
      (node (ref "R11") (pin "1") (pinfunction "1_1") (pintype "input"))
    )
    (net (code "28") (name "Net-(LED4-Pad3)") (class "Default")
      (node (ref "LED4") (pin "3") (pinfunction "3_3") (pintype "unspecified"))
      (node (ref "R9") (pin "2") (pinfunction "2_2") (pintype "input"))
    )
    (net (code "29") (name "Net-(LED4-Pad4)") (class "Default")
      (node (ref "LED4") (pin "4") (pinfunction "4_4") (pintype "unspecified"))
      (node (ref "R5") (pin "2") (pinfunction "2_2") (pintype "input"))
    )
    (net (code "30") (name "Net-(Q1-Pad1)") (class "Default")
      (node (ref "Q1") (pin "1") (pinfunction "1_1") (pintype "input"))
      (node (ref "R3") (pin "1") (pinfunction "1_1") (pintype "input"))
    )
    (net (code "31") (name "Net-(Q2-Pad1)") (class "Default")
      (node (ref "Q2") (pin "1") (pinfunction "1_1") (pintype "input"))
      (node (ref "R4") (pin "1") (pinfunction "1_1") (pintype "input"))
    )
    (net (code "32") (name "Net-(Q3-D)") (class "Default")
      (node (ref "PYRO2") (pin "1") (pinfunction "1_1") (pintype "unspecified"))
      (node (ref "Q3") (pin "3") (pinfunction "D_3") (pintype "unspecified"))
    )
    (net (code "33") (name "Net-(Q3-G)") (class "Default")
      (node (ref "Q3") (pin "1") (pinfunction "G_1") (pintype "unspecified"))
      (node (ref "R18") (pin "2") (pinfunction "2_2") (pintype "input"))
    )
    (net (code "34") (name "Net-(Q4-D)") (class "Default")
      (node (ref "PYRO1") (pin "1") (pinfunction "1_1") (pintype "unspecified"))
      (node (ref "Q4") (pin "3") (pinfunction "D_3") (pintype "unspecified"))
    )
    (net (code "35") (name "Net-(Q4-G)") (class "Default")
      (node (ref "Q4") (pin "1") (pinfunction "G_1") (pintype "unspecified"))
      (node (ref "R13") (pin "2") (pinfunction "2_2") (pintype "input"))
    )
    (net (code "36") (name "Net-(Q5-G)") (class "Default")
      (node (ref "Q5") (pin "1") (pinfunction "G_1") (pintype "unspecified"))
      (node (ref "R12") (pin "2") (pinfunction "2_2") (pintype "input"))
    )
    (net (code "37") (name "Net-(Q9-B)") (class "Default")
      (node (ref "Q9") (pin "1") (pinfunction "B_1") (pintype "input"))
      (node (ref "R19") (pin "2") (pinfunction "2_2") (pintype "input"))
    )
    (net (code "38") (name "Net-(RF1-CONT)") (class "Default")
      (node (ref "C14") (pin "2") (pinfunction "2_2") (pintype "input"))
      (node (ref "RF1") (pin "2") (pinfunction "CONT_2") (pintype "unspecified"))
    )
    (net (code "39") (name "Net-(U8-RFIN)") (class "Default")
      (node (ref "L1") (pin "1") (pinfunction "1_1") (pintype "unspecified"))
      (node (ref "U8") (pin "3") (pinfunction "RFIN_3") (pintype "unspecified"))
    )
    (net (code "40") (name "RF") (class "Default")
      (node (ref "U6") (pin "11") (pinfunction "RF_IN_11") (pintype "unspecified"))
      (node (ref "U8") (pin "6") (pinfunction "RFOUT_6") (pintype "unspecified"))
    )
    (net (code "41") (name "RTS") (class "Default")
      (node (ref "Q1") (pin "2") (pinfunction "2_2") (pintype "input"))
      (node (ref "R4") (pin "2") (pinfunction "2_2") (pintype "input"))
      (node (ref "U1") (pin "14") (pinfunction "RTS#_14") (pintype "unspecified"))
    )
    (net (code "42") (name "RXD") (class "Default")
      (node (ref "H3") (pin "1") (pinfunction "1_1") (pintype "unspecified"))
      (node (ref "R9") (pin "1") (pinfunction "1_1") (pintype "input"))
      (node (ref "U1") (pin "3") (pinfunction "RXD_3") (pintype "unspecified"))
      (node (ref "U4") (pin "35") (pinfunction "TXD0_35") (pintype "unspecified"))
      (node (ref "U6") (pin "3") (pinfunction "RXD_3") (pintype "unspecified"))
    )
    (net (code "43") (name "SCL") (class "Default")
      (node (ref "CN2") (pin "2") (pinfunction "2_2") (pintype "unspecified"))
      (node (ref "H6") (pin "3") (pinfunction "3_3") (pintype "unspecified"))
      (node (ref "H8") (pin "3") (pinfunction "3_3") (pintype "unspecified"))
      (node (ref "R21") (pin "1") (pinfunction "1_1") (pintype "input"))
      (node (ref "R7") (pin "2") (pinfunction "2_2") (pintype "input"))
      (node (ref "U2") (pin "4") (pinfunction "SCK_4") (pintype "unspecified"))
      (node (ref "U4") (pin "33") (pinfunction "IO21_33") (pintype "unspecified"))
      (node (ref "U7") (pin "13") (pinfunction "SCL_13") (pintype "unspecified"))
    )
    (net (code "44") (name "SDA") (class "Default")
      (node (ref "CN2") (pin "1") (pinfunction "1_1") (pintype "unspecified"))
      (node (ref "H6") (pin "4") (pinfunction "4_4") (pintype "unspecified"))
      (node (ref "H8") (pin "4") (pinfunction "4_4") (pintype "unspecified"))
      (node (ref "R20") (pin "2") (pinfunction "2_2") (pintype "input"))
      (node (ref "R6") (pin "2") (pinfunction "2_2") (pintype "input"))
      (node (ref "U2") (pin "3") (pinfunction "SDI_3") (pintype "unspecified"))
      (node (ref "U4") (pin "36") (pinfunction "IO22_36") (pintype "unspecified"))
      (node (ref "U7") (pin "14") (pinfunction "SDA_14") (pintype "unspecified"))
    )
    (net (code "45") (name "TXD") (class "Default")
      (node (ref "H3") (pin "2") (pinfunction "2_2") (pintype "unspecified"))
      (node (ref "R5") (pin "1") (pinfunction "1_1") (pintype "input"))
      (node (ref "U1") (pin "2") (pinfunction "TXD_2") (pintype "unspecified"))
      (node (ref "U4") (pin "34") (pinfunction "RXD0_34") (pintype "unspecified"))
      (node (ref "U6") (pin "2") (pinfunction "TXD_2") (pintype "unspecified"))
    )
    (net (code "46") (name "VCC") (class "Default")
      (node (ref "H4") (pin "2") (pinfunction "2_2") (pintype "unspecified"))
      (node (ref "Q5") (pin "2") (pinfunction "S_2") (pintype "unspecified"))
    )
    (net (code "47") (name "VIN") (class "Default")
      (node (ref "Q5") (pin "3") (pinfunction "D_3") (pintype "unspecified"))
      (node (ref "U10") (pin "1") (pinfunction "1_1") (pintype "unspecified"))
    )
    (net (code "48") (name "pulse") (class "Default")
      (node (ref "R11") (pin "2") (pinfunction "2_2") (pintype "input"))
      (node (ref "U6") (pin "4") (pinfunction "1PPS_4") (pintype "unspecified"))
    )
    (net (code "49") (name "unconnected-(BOOT-Pad3)") (class "Default")
      (node (ref "BOOT") (pin "3") (pinfunction "3_3") (pintype "unspecified+no_connect"))
    )
    (net (code "50") (name "unconnected-(BOOT-Pad4)") (class "Default")
      (node (ref "BOOT") (pin "4") (pinfunction "4_4") (pintype "unspecified+no_connect"))
    )
    (net (code "51") (name "unconnected-(BUZZER3-Pad3)") (class "Default")
      (node (ref "BUZZER3") (pin "3") (pinfunction "3_3") (pintype "unspecified+no_connect"))
    )
    (net (code "52") (name "unconnected-(BUZZER3-Pad4)") (class "Default")
      (node (ref "BUZZER3") (pin "4") (pinfunction "4_4") (pintype "unspecified+no_connect"))
    )
    (net (code "53") (name "unconnected-(LED2-DOUT-Pad2)") (class "Default")
      (node (ref "LED2") (pin "2") (pinfunction "DOUT_2") (pintype "unspecified+no_connect"))
    )
    (net (code "54") (name "unconnected-(RST-Pad3)") (class "Default")
      (node (ref "RST") (pin "3") (pinfunction "3_3") (pintype "unspecified+no_connect"))
    )
    (net (code "55") (name "unconnected-(RST-Pad4)") (class "Default")
      (node (ref "RST") (pin "4") (pinfunction "4_4") (pintype "unspecified+no_connect"))
    )
    (net (code "56") (name "unconnected-(U1-CTS#-Pad9)") (class "Default")
      (node (ref "U1") (pin "9") (pinfunction "CTS#_9") (pintype "unspecified+no_connect"))
    )
    (net (code "57") (name "unconnected-(U1-DCD#-Pad12)") (class "Default")
      (node (ref "U1") (pin "12") (pinfunction "DCD#_12") (pintype "unspecified+no_connect"))
    )
    (net (code "58") (name "unconnected-(U1-DSR#-Pad10)") (class "Default")
      (node (ref "U1") (pin "10") (pinfunction "DSR#_10") (pintype "unspecified+no_connect"))
    )
    (net (code "59") (name "unconnected-(U1-NC.-Pad7)") (class "Default")
      (node (ref "U1") (pin "7") (pinfunction "NC._7") (pintype "unspecified+no_connect"))
    )
    (net (code "60") (name "unconnected-(U1-NC.-Pad8)") (class "Default")
      (node (ref "U1") (pin "8") (pinfunction "NC._8") (pintype "unspecified+no_connect"))
    )
    (net (code "61") (name "unconnected-(U1-R232-Pad15)") (class "Default")
      (node (ref "U1") (pin "15") (pinfunction "R232_15") (pintype "unspecified+no_connect"))
    )
    (net (code "62") (name "unconnected-(U1-RI#-Pad11)") (class "Default")
      (node (ref "U1") (pin "11") (pinfunction "RI#_11") (pintype "unspecified+no_connect"))
    )
    (net (code "63") (name "unconnected-(U2-SDO-Pad5)") (class "Default")
      (node (ref "U2") (pin "5") (pinfunction "SDO_5") (pintype "unspecified+no_connect"))
    )
    (net (code "64") (name "unconnected-(U3-GND-Pad2)") (class "Default")
      (node (ref "U3") (pin "2") (pinfunction "GND_2") (pintype "unspecified+no_connect"))
    )
    (net (code "65") (name "unconnected-(U4-GND-Pad15)") (class "Default")
      (node (ref "U4") (pin "15") (pinfunction "GND_15") (pintype "unspecified+no_connect"))
    )
    (net (code "66") (name "unconnected-(U4-IO4-Pad26)") (class "Default")
      (node (ref "U4") (pin "26") (pinfunction "IO4_26") (pintype "unspecified+no_connect"))
    )
    (net (code "67") (name "unconnected-(U4-IO5-Pad29)") (class "Default")
      (node (ref "U4") (pin "29") (pinfunction "IO5_29") (pintype "unspecified+no_connect"))
    )
    (net (code "68") (name "unconnected-(U4-IO18-Pad30)") (class "Default")
      (node (ref "U4") (pin "30") (pinfunction "IO18_30") (pintype "unspecified+no_connect"))
    )
    (net (code "69") (name "unconnected-(U4-IO19-Pad31)") (class "Default")
      (node (ref "U4") (pin "31") (pinfunction "IO19_31") (pintype "unspecified+no_connect"))
    )
    (net (code "70") (name "unconnected-(U4-IO23-Pad37)") (class "Default")
      (node (ref "U4") (pin "37") (pinfunction "IO23_37") (pintype "unspecified+no_connect"))
    )
    (net (code "71") (name "unconnected-(U4-IO26-Pad11)") (class "Default")
      (node (ref "U4") (pin "11") (pinfunction "IO26_11") (pintype "unspecified+no_connect"))
    )
    (net (code "72") (name "unconnected-(U4-IO34-Pad6)") (class "Default")
      (node (ref "U4") (pin "6") (pinfunction "IO34_6") (pintype "unspecified+no_connect"))
    )
    (net (code "73") (name "unconnected-(U4-IO35-Pad7)") (class "Default")
      (node (ref "U4") (pin "7") (pinfunction "IO35_7") (pintype "unspecified+no_connect"))
    )
    (net (code "74") (name "unconnected-(U4-NC-Pad17)") (class "Default")
      (node (ref "U4") (pin "17") (pinfunction "NC_17") (pintype "unspecified+no_connect"))
    )
    (net (code "75") (name "unconnected-(U4-NC-Pad18)") (class "Default")
      (node (ref "U4") (pin "18") (pinfunction "NC_18") (pintype "unspecified+no_connect"))
    )
    (net (code "76") (name "unconnected-(U4-NC-Pad19)") (class "Default")
      (node (ref "U4") (pin "19") (pinfunction "NC_19") (pintype "unspecified+no_connect"))
    )
    (net (code "77") (name "unconnected-(U4-NC-Pad20)") (class "Default")
      (node (ref "U4") (pin "20") (pinfunction "NC_20") (pintype "unspecified+no_connect"))
    )
    (net (code "78") (name "unconnected-(U4-NC-Pad21)") (class "Default")
      (node (ref "U4") (pin "21") (pinfunction "NC_21") (pintype "unspecified+no_connect"))
    )
    (net (code "79") (name "unconnected-(U4-NC-Pad22)") (class "Default")
      (node (ref "U4") (pin "22") (pinfunction "NC_22") (pintype "unspecified+no_connect"))
    )
    (net (code "80") (name "unconnected-(U4-NC-Pad32)") (class "Default")
      (node (ref "U4") (pin "32") (pinfunction "NC_32") (pintype "unspecified+no_connect"))
    )
    (net (code "81") (name "unconnected-(U4-SENSOR_VN-Pad5)") (class "Default")
      (node (ref "U4") (pin "5") (pinfunction "SENSOR_VN_5") (pintype "unspecified+no_connect"))
    )
    (net (code "82") (name "unconnected-(U4-SENSOR_VP-Pad4)") (class "Default")
      (node (ref "U4") (pin "4") (pinfunction "SENSOR_VP_4") (pintype "unspecified+no_connect"))
    )
    (net (code "83") (name "unconnected-(U6-NC-Pad7)") (class "Default")
      (node (ref "U6") (pin "7") (pinfunction "NC_7") (pintype "unspecified+no_connect"))
    )
    (net (code "84") (name "unconnected-(U6-NC-Pad13)") (class "Default")
      (node (ref "U6") (pin "13") (pinfunction "NC_13") (pintype "unspecified+no_connect"))
    )
    (net (code "85") (name "unconnected-(U6-NRESET-Pad9)") (class "Default")
      (node (ref "U6") (pin "9") (pinfunction "NRESET_9") (pintype "unspecified+no_connect"))
    )
    (net (code "86") (name "unconnected-(U6-ON{slash}OFF-Pad5)") (class "Default")
      (node (ref "U6") (pin "5") (pinfunction "ON/OFF_5") (pintype "unspecified+no_connect"))
    )
    (net (code "87") (name "unconnected-(U6-Reserved-Pad15)") (class "Default")
      (node (ref "U6") (pin "15") (pinfunction "Reserved_15") (pintype "unspecified+no_connect"))
    )
    (net (code "88") (name "unconnected-(U6-Reserved-Pad18)") (class "Default")
      (node (ref "U6") (pin "18") (pinfunction "Reserved_18") (pintype "unspecified+no_connect"))
    )
    (net (code "89") (name "unconnected-(U6-SCL-Pad17)") (class "Default")
      (node (ref "U6") (pin "17") (pinfunction "SCL_17") (pintype "unspecified+no_connect"))
    )
    (net (code "90") (name "unconnected-(U6-SDA-Pad16)") (class "Default")
      (node (ref "U6") (pin "16") (pinfunction "SDA_16") (pintype "unspecified+no_connect"))
    )
    (net (code "91") (name "unconnected-(U6-VBAT-Pad6)") (class "Default")
      (node (ref "U6") (pin "6") (pinfunction "VBAT_6") (pintype "unspecified+no_connect"))
    )
    (net (code "92") (name "unconnected-(U6-VCC_RF-Pad14)") (class "Default")
      (node (ref "U6") (pin "14") (pinfunction "VCC_RF_14") (pintype "unspecified+no_connect"))
    )
    (net (code "93") (name "unconnected-(U7-INT1-Pad4)") (class "Default")
      (node (ref "U7") (pin "4") (pinfunction "INT1_4") (pintype "unspecified+no_connect"))
    )
    (net (code "94") (name "unconnected-(U7-OCS_AUX-Pad10)") (class "Default")
      (node (ref "U7") (pin "10") (pinfunction "OCS_AUX_10") (pintype "unspecified+no_connect"))
    )
    (net (code "95") (name "unconnected-(U7-SDO_AUX-Pad11)") (class "Default")
      (node (ref "U7") (pin "11") (pinfunction "SDO_AUX_11") (pintype "unspecified+no_connect"))
    )
    (net (code "96") (name "unconnected-(USB4-SBU1-PadA8)") (class "Default")
      (node (ref "USB4") (pin "A8") (pinfunction "SBU1_A8") (pintype "unspecified+no_connect"))
    )
    (net (code "97") (name "unconnected-(USB4-SBU2-PadB8)") (class "Default")
      (node (ref "USB4") (pin "B8") (pinfunction "SBU2_B8") (pintype "unspecified+no_connect"))
    )
  )
)
